# driver.net
KiCad netlist of a schematic drawn in Altium Designer
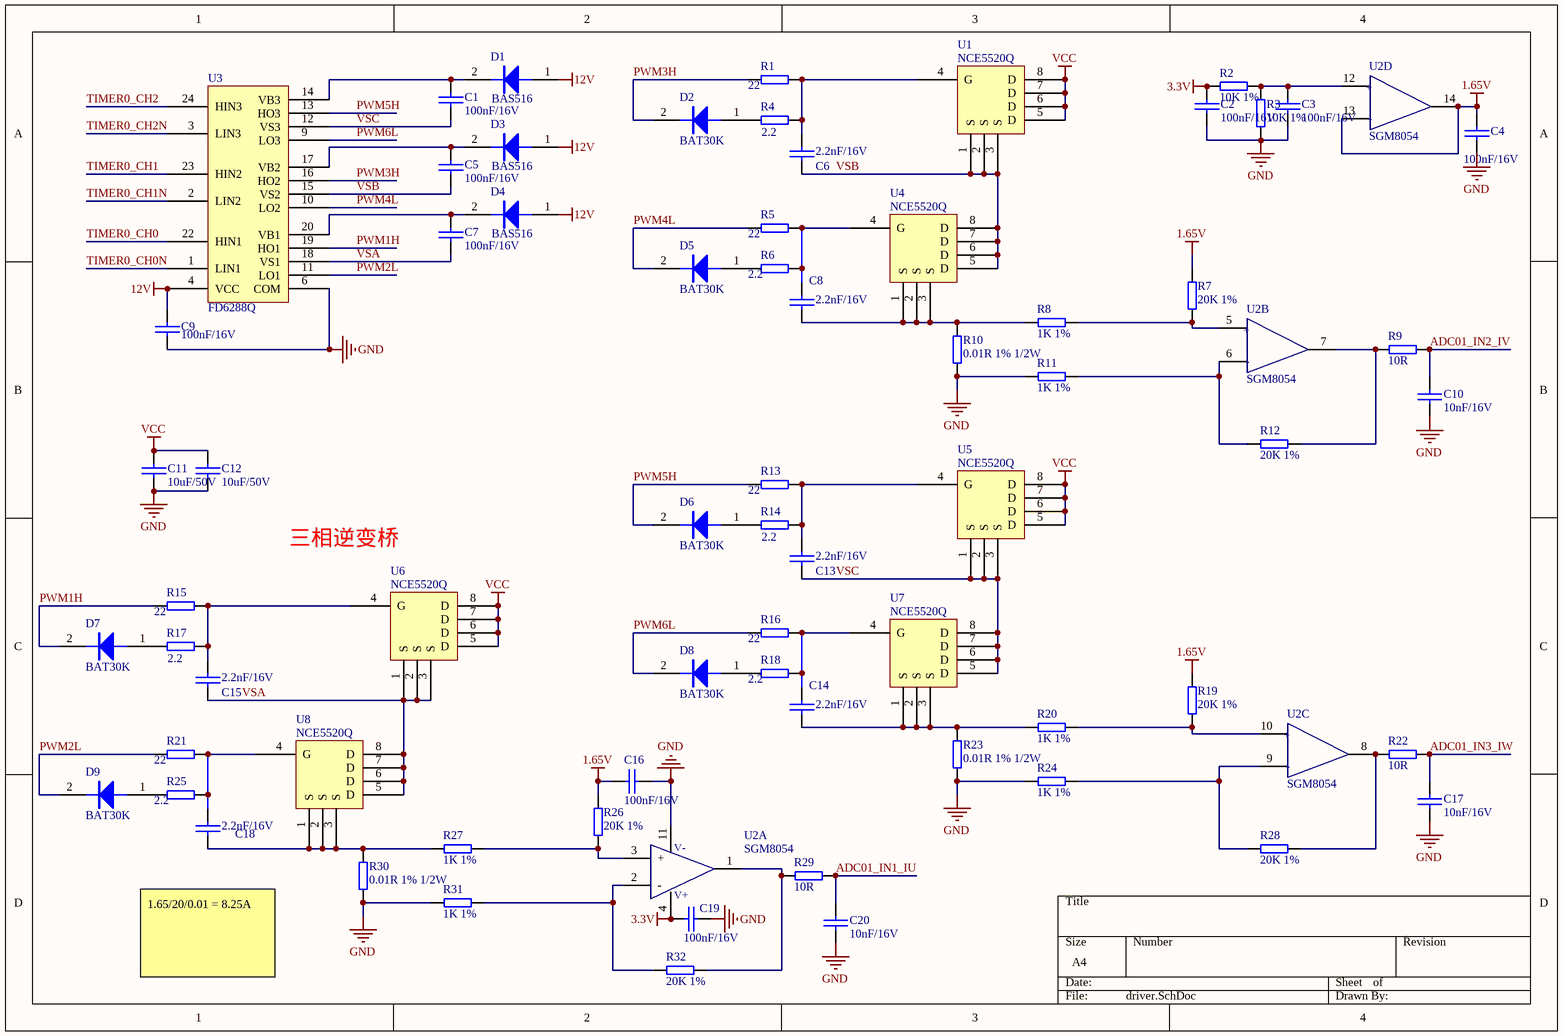
[diagram p0: driver.SchDoc]

(export (version "E")
  (design (tool "Eeschema 10.0.6"))
  (components
    (comp (ref "C1")
      (value "100nF/16V")
      (footprint "C0402")
      (description "Capacitor")
      (libsource (lib "*") (part "CAP"))
    )
    (comp (ref "C2")
      (value "100nF/16V")
      (footprint "C0402")
      (description "Capacitor")
      (libsource (lib "*") (part "CAP"))
    )
    (comp (ref "C3")
      (value "100nF/16V")
      (footprint "C0402")
      (description "Capacitor")
      (libsource (lib "*") (part "CAP"))
    )
    (comp (ref "C4")
      (value "100nF/16V")
      (footprint "C0402")
      (description "Capacitor")
      (libsource (lib "*") (part "CAP"))
    )
    (comp (ref "C5")
      (value "100nF/16V")
      (footprint "C0402")
      (description "Capacitor")
      (libsource (lib "*") (part "CAP"))
    )
    (comp (ref "C6")
      (value "2.2nF/16V")
      (footprint "C0402")
      (description "Capacitor")
      (libsource (lib "*") (part "CAP"))
    )
    (comp (ref "C7")
      (value "100nF/16V")
      (footprint "C0402")
      (description "Capacitor")
      (libsource (lib "*") (part "CAP"))
    )
    (comp (ref "C8")
      (value "2.2nF/16V")
      (footprint "C0402")
      (description "Capacitor")
      (libsource (lib "*") (part "CAP"))
    )
    (comp (ref "C9")
      (value "100nF/16V")
      (footprint "C0402")
      (description "Capacitor")
      (libsource (lib "*") (part "CAP"))
    )
    (comp (ref "C10")
      (value "10nF/16V")
      (footprint "C0402")
      (description "Capacitor")
      (libsource (lib "*") (part "CAP"))
    )
    (comp (ref "C11")
      (value "10uF/50V")
      (footprint "C1206")
      (description "Capacitor")
      (libsource (lib "*") (part "CAP"))
    )
    (comp (ref "C12")
      (value "10uF/50V")
      (footprint "C1206")
      (description "Capacitor")
      (libsource (lib "*") (part "CAP"))
    )
    (comp (ref "C13")
      (value "2.2nF/16V")
      (footprint "C0402")
      (description "Capacitor")
      (libsource (lib "*") (part "CAP"))
    )
    (comp (ref "C14")
      (value "2.2nF/16V")
      (footprint "C0402")
      (description "Capacitor")
      (libsource (lib "*") (part "CAP"))
    )
    (comp (ref "C15")
      (value "2.2nF/16V")
      (footprint "C0402")
      (description "Capacitor")
      (libsource (lib "*") (part "CAP"))
    )
    (comp (ref "C16")
      (value "100nF/16V")
      (footprint "C0402")
      (description "Capacitor")
      (libsource (lib "*") (part "CAP"))
    )
    (comp (ref "C17")
      (value "10nF/16V")
      (footprint "C0402")
      (description "Capacitor")
      (libsource (lib "*") (part "CAP"))
    )
    (comp (ref "C18")
      (value "2.2nF/16V")
      (footprint "C0402")
      (description "Capacitor")
      (libsource (lib "*") (part "CAP"))
    )
    (comp (ref "C19")
      (value "100nF/16V")
      (footprint "C0402")
      (description "Capacitor")
      (libsource (lib "*") (part "CAP"))
    )
    (comp (ref "C20")
      (value "10nF/16V")
      (footprint "C0402")
      (description "Capacitor")
      (libsource (lib "*") (part "CAP"))
    )
    (comp (ref "D1") (value "BAS516") (footprint "SOD-523/SC-79") (libsource (lib "*") (part "DIODE")))
    (comp (ref "D2") (value "BAT30K") (footprint "SOD-523/SC-79") (libsource (lib "*") (part "DIODE")))
    (comp (ref "D3") (value "BAS516") (footprint "SOD-523/SC-79") (libsource (lib "*") (part "DIODE")))
    (comp (ref "D4") (value "BAS516") (footprint "SOD-523/SC-79") (libsource (lib "*") (part "DIODE")))
    (comp (ref "D5") (value "BAT30K") (footprint "SOD-523/SC-79") (libsource (lib "*") (part "DIODE")))
    (comp (ref "D6") (value "BAT30K") (footprint "SOD-523/SC-79") (libsource (lib "*") (part "DIODE")))
    (comp (ref "D7") (value "BAT30K") (footprint "SOD-523/SC-79") (libsource (lib "*") (part "DIODE")))
    (comp (ref "D8") (value "BAT30K") (footprint "SOD-523/SC-79") (libsource (lib "*") (part "DIODE")))
    (comp (ref "D9") (value "BAT30K") (footprint "SOD-523/SC-79") (libsource (lib "*") (part "DIODE")))
    (comp (ref "R1") (value "22") (footprint "R0402") (libsource (lib "*") (part "R")))
    (comp (ref "R2") (value "10K 1%") (footprint "R0402") (libsource (lib "zijianku") (part "Resistance")))
    (comp (ref "R3") (value "10K 1%") (footprint "R0402") (libsource (lib "zijianku") (part "Resistance")))
    (comp (ref "R4") (value "2.2") (footprint "R0402") (libsource (lib "*") (part "R")))
    (comp (ref "R5") (value "22") (footprint "R0402") (libsource (lib "*") (part "R")))
    (comp (ref "R6") (value "2.2") (footprint "R0402") (libsource (lib "*") (part "R")))
    (comp (ref "R7") (value "20K 1%") (footprint "R0402") (libsource (lib "zijianku") (part "Resistance")))
    (comp (ref "R8") (value "1K 1%") (footprint "R0402") (libsource (lib "zijianku") (part "Resistance")))
    (comp (ref "R9") (value "10R") (footprint "R0402") (libsource (lib "zijianku") (part "Resistance")))
    (comp (ref "R10")
      (value "0.01R 1% 1/2W")
      (footprint "R0805")
      (libsource (lib "zijianku") (part "Resistance"))
    )
    (comp (ref "R11") (value "1K 1%") (footprint "R0402") (libsource (lib "zijianku") (part "Resistance")))
    (comp (ref "R12") (value "20K 1%") (footprint "R0402") (libsource (lib "zijianku") (part "Resistance")))
    (comp (ref "R13") (value "22") (footprint "R0402") (libsource (lib "*") (part "R")))
    (comp (ref "R14") (value "2.2") (footprint "R0402") (libsource (lib "*") (part "R")))
    (comp (ref "R15") (value "22") (footprint "R0402") (libsource (lib "*") (part "R")))
    (comp (ref "R16") (value "22") (footprint "R0402") (libsource (lib "*") (part "R")))
    (comp (ref "R17") (value "2.2") (footprint "R0402") (libsource (lib "*") (part "R")))
    (comp (ref "R18") (value "2.2") (footprint "R0402") (libsource (lib "*") (part "R")))
    (comp (ref "R19") (value "20K 1%") (footprint "R0402") (libsource (lib "zijianku") (part "Resistance")))
    (comp (ref "R20") (value "1K 1%") (footprint "R0402") (libsource (lib "zijianku") (part "Resistance")))
    (comp (ref "R21") (value "22") (footprint "R0402") (libsource (lib "*") (part "R")))
    (comp (ref "R22") (value "10R") (footprint "R0402") (libsource (lib "zijianku") (part "Resistance")))
    (comp (ref "R23")
      (value "0.01R 1% 1/2W")
      (footprint "R0805")
      (libsource (lib "zijianku") (part "Resistance"))
    )
    (comp (ref "R24") (value "1K 1%") (footprint "R0402") (libsource (lib "zijianku") (part "Resistance")))
    (comp (ref "R25") (value "2.2") (footprint "R0402") (libsource (lib "*") (part "R")))
    (comp (ref "R26") (value "20K 1%") (footprint "R0402") (libsource (lib "zijianku") (part "Resistance")))
    (comp (ref "R27") (value "1K 1%") (footprint "R0402") (libsource (lib "zijianku") (part "Resistance")))
    (comp (ref "R28") (value "20K 1%") (footprint "R0402") (libsource (lib "zijianku") (part "Resistance")))
    (comp (ref "R29") (value "10R") (footprint "R0402") (libsource (lib "zijianku") (part "Resistance")))
    (comp (ref "R30")
      (value "0.01R 1% 1/2W")
      (footprint "R0805")
      (libsource (lib "zijianku") (part "Resistance"))
    )
    (comp (ref "R31") (value "1K 1%") (footprint "R0402") (libsource (lib "zijianku") (part "Resistance")))
    (comp (ref "R32") (value "20K 1%") (footprint "R0402") (libsource (lib "zijianku") (part "Resistance")))
    (comp (ref "U1") (value "NCE5520Q") (footprint "DFN3X3-8L") (libsource (lib "*") (part "SI7465DP")))
    (comp (ref "U2") (value "SGM8054") (footprint "TSSOP-14") (libsource (lib "zijianku") (part "SGM8054")))
    (comp (ref "U3")
      (value "FD6288Q")
      (footprint "QFN_P0.5_24")
      (description "峰岹科技")
      (libsource (lib "zijianku") (part "FD6288Q"))
    )
    (comp (ref "U4") (value "NCE5520Q") (footprint "DFN3X3-8L") (libsource (lib "*") (part "SI7465DP")))
    (comp (ref "U5") (value "NCE5520Q") (footprint "DFN3X3-8L") (libsource (lib "*") (part "SI7465DP")))
    (comp (ref "U6") (value "NCE5520Q") (footprint "DFN3X3-8L") (libsource (lib "*") (part "SI7465DP")))
    (comp (ref "U7") (value "NCE5520Q") (footprint "DFN3X3-8L") (libsource (lib "*") (part "SI7465DP")))
    (comp (ref "U8") (value "NCE5520Q") (footprint "DFN3X3-8L") (libsource (lib "*") (part "SI7465DP")))
  )
  (nets
    (net (code "1") (name "/ADC01_IN1_IU") (class "Default")
      (node (ref "C20") (pin "1") (pinfunction "1_1") (pintype "passive"))
      (node (ref "R29") (pin "1") (pintype "passive"))
    )
    (net (code "2") (name "/ADC01_IN2_IV") (class "Default")
      (node (ref "C10") (pin "1") (pinfunction "1_1") (pintype "passive"))
      (node (ref "R9") (pin "1") (pintype "passive"))
    )
    (net (code "3") (name "/ADC01_IN3_IW") (class "Default")
      (node (ref "C17") (pin "1") (pinfunction "1_1") (pintype "passive"))
      (node (ref "R22") (pin "1") (pintype "passive"))
    )
    (net (code "4") (name "/PWM1H") (class "Default")
      (node (ref "D7") (pin "2") (pinfunction "K_2") (pintype "passive"))
      (node (ref "R15") (pin "2") (pinfunction "2_2") (pintype "passive"))
      (node (ref "U3") (pin "19") (pinfunction "HO1_19") (pintype "passive"))
    )
    (net (code "5") (name "/PWM2L") (class "Default")
      (node (ref "D9") (pin "2") (pinfunction "K_2") (pintype "passive"))
      (node (ref "R21") (pin "2") (pinfunction "2_2") (pintype "passive"))
      (node (ref "U3") (pin "11") (pinfunction "LO1_11") (pintype "passive"))
    )
    (net (code "6") (name "/PWM3H") (class "Default")
      (node (ref "D2") (pin "2") (pinfunction "K_2") (pintype "passive"))
      (node (ref "R1") (pin "2") (pinfunction "2_2") (pintype "passive"))
      (node (ref "U3") (pin "16") (pinfunction "HO2_16") (pintype "passive"))
    )
    (net (code "7") (name "/PWM4L") (class "Default")
      (node (ref "D5") (pin "2") (pinfunction "K_2") (pintype "passive"))
      (node (ref "R5") (pin "2") (pinfunction "2_2") (pintype "passive"))
      (node (ref "U3") (pin "10") (pinfunction "LO2_10") (pintype "passive"))
    )
    (net (code "8") (name "/PWM5H") (class "Default")
      (node (ref "D6") (pin "2") (pinfunction "K_2") (pintype "passive"))
      (node (ref "R13") (pin "2") (pinfunction "2_2") (pintype "passive"))
      (node (ref "U3") (pin "13") (pinfunction "HO3_13") (pintype "passive"))
    )
    (net (code "9") (name "/PWM6L") (class "Default")
      (node (ref "D8") (pin "2") (pinfunction "K_2") (pintype "passive"))
      (node (ref "R16") (pin "2") (pinfunction "2_2") (pintype "passive"))
      (node (ref "U3") (pin "9") (pinfunction "LO3_9") (pintype "passive"))
    )
    (net (code "10") (name "/TIMER0_CH0") (class "Default")
      (node (ref "U3") (pin "22") (pinfunction "HIN1_22") (pintype "passive"))
    )
    (net (code "11") (name "/TIMER0_CH0N") (class "Default")
      (node (ref "U3") (pin "1") (pinfunction "LIN1_1") (pintype "passive"))
    )
    (net (code "12") (name "/TIMER0_CH1") (class "Default")
      (node (ref "U3") (pin "23") (pinfunction "HIN2_23") (pintype "passive"))
    )
    (net (code "13") (name "/TIMER0_CH1N") (class "Default")
      (node (ref "U3") (pin "2") (pinfunction "LIN2_2") (pintype "passive"))
    )
    (net (code "14") (name "/TIMER0_CH2") (class "Default")
      (node (ref "U3") (pin "24") (pinfunction "HIN3_24") (pintype "passive"))
    )
    (net (code "15") (name "/TIMER0_CH2N") (class "Default")
      (node (ref "U3") (pin "3") (pinfunction "LIN3_3") (pintype "passive"))
    )
    (net (code "16") (name "/VSA") (class "Default")
      (node (ref "C15") (pin "2") (pinfunction "2_2") (pintype "passive"))
      (node (ref "C7") (pin "1") (pinfunction "1_1") (pintype "passive"))
      (node (ref "U3") (pin "18") (pinfunction "VS1_18") (pintype "passive"))
      (node (ref "U6") (pin "1") (pinfunction "S_1") (pintype "passive"))
      (node (ref "U6") (pin "2") (pinfunction "S_2") (pintype "passive"))
      (node (ref "U6") (pin "3") (pinfunction "S_3") (pintype "passive"))
      (node (ref "U8") (pin "5") (pinfunction "D_5") (pintype "passive"))
      (node (ref "U8") (pin "6") (pinfunction "D_6") (pintype "passive"))
      (node (ref "U8") (pin "7") (pinfunction "D_7") (pintype "passive"))
      (node (ref "U8") (pin "8") (pinfunction "D_8") (pintype "passive"))
    )
    (net (code "17") (name "/VSB") (class "Default")
      (node (ref "C5") (pin "1") (pinfunction "1_1") (pintype "passive"))
      (node (ref "C6") (pin "2") (pinfunction "2_2") (pintype "passive"))
      (node (ref "U1") (pin "1") (pinfunction "S_1") (pintype "passive"))
      (node (ref "U1") (pin "2") (pinfunction "S_2") (pintype "passive"))
      (node (ref "U1") (pin "3") (pinfunction "S_3") (pintype "passive"))
      (node (ref "U3") (pin "15") (pinfunction "VS2_15") (pintype "passive"))
      (node (ref "U4") (pin "5") (pinfunction "D_5") (pintype "passive"))
      (node (ref "U4") (pin "6") (pinfunction "D_6") (pintype "passive"))
      (node (ref "U4") (pin "7") (pinfunction "D_7") (pintype "passive"))
      (node (ref "U4") (pin "8") (pinfunction "D_8") (pintype "passive"))
    )
    (net (code "18") (name "/VSC") (class "Default")
      (node (ref "C1") (pin "1") (pinfunction "1_1") (pintype "passive"))
      (node (ref "C13") (pin "2") (pinfunction "2_2") (pintype "passive"))
      (node (ref "U3") (pin "12") (pinfunction "VS3_12") (pintype "passive"))
      (node (ref "U5") (pin "1") (pinfunction "S_1") (pintype "passive"))
      (node (ref "U5") (pin "2") (pinfunction "S_2") (pintype "passive"))
      (node (ref "U5") (pin "3") (pinfunction "S_3") (pintype "passive"))
      (node (ref "U7") (pin "5") (pinfunction "D_5") (pintype "passive"))
      (node (ref "U7") (pin "6") (pinfunction "D_6") (pintype "passive"))
      (node (ref "U7") (pin "7") (pinfunction "D_7") (pintype "passive"))
      (node (ref "U7") (pin "8") (pinfunction "D_8") (pintype "passive"))
    )
    (net (code "19") (name "1.65V") (class "Default")
      (node (ref "C16") (pin "2") (pinfunction "2_2") (pintype "passive"))
      (node (ref "C4") (pin "1") (pinfunction "1_1") (pintype "passive"))
      (node (ref "R19") (pin "1") (pintype "passive"))
      (node (ref "R26") (pin "1") (pintype "passive"))
      (node (ref "R7") (pin "1") (pintype "passive"))
      (node (ref "U2") (pin "13") (pinfunction "-_13") (pintype "passive"))
      (node (ref "U2") (pin "14") (pinfunction "OUT2_14") (pintype "passive"))
    )
    (net (code "20") (name "3.3V") (class "Default")
      (node (ref "C19") (pin "2") (pinfunction "2_2") (pintype "passive"))
      (node (ref "C2") (pin "1") (pinfunction "1_1") (pintype "passive"))
      (node (ref "R2") (pin "1") (pintype "passive"))
      (node (ref "U2") (pin "4") (pinfunction "V+_4") (pintype "passive"))
    )
    (net (code "21") (name "12V") (class "Default")
      (node (ref "C9") (pin "2") (pinfunction "2_2") (pintype "passive"))
      (node (ref "D1") (pin "1") (pinfunction "A_1") (pintype "passive"))
      (node (ref "D3") (pin "1") (pinfunction "A_1") (pintype "passive"))
      (node (ref "D4") (pin "1") (pinfunction "A_1") (pintype "passive"))
      (node (ref "U3") (pin "4") (pinfunction "VCC_4") (pintype "passive"))
    )
    (net (code "22") (name "GND") (class "Default")
      (node (ref "C10") (pin "2") (pinfunction "2_2") (pintype "passive"))
      (node (ref "C11") (pin "2") (pinfunction "2_2") (pintype "passive"))
      (node (ref "C12") (pin "2") (pinfunction "2_2") (pintype "passive"))
      (node (ref "C16") (pin "1") (pinfunction "1_1") (pintype "passive"))
      (node (ref "C17") (pin "2") (pinfunction "2_2") (pintype "passive"))
      (node (ref "C19") (pin "1") (pinfunction "1_1") (pintype "passive"))
      (node (ref "C2") (pin "2") (pinfunction "2_2") (pintype "passive"))
      (node (ref "C20") (pin "2") (pinfunction "2_2") (pintype "passive"))
      (node (ref "C3") (pin "2") (pinfunction "2_2") (pintype "passive"))
      (node (ref "C4") (pin "2") (pinfunction "2_2") (pintype "passive"))
      (node (ref "C9") (pin "1") (pinfunction "1_1") (pintype "passive"))
      (node (ref "R10") (pin "2") (pintype "passive"))
      (node (ref "R11") (pin "2") (pintype "passive"))
      (node (ref "R23") (pin "2") (pintype "passive"))
      (node (ref "R24") (pin "2") (pintype "passive"))
      (node (ref "R3") (pin "2") (pintype "passive"))
      (node (ref "R30") (pin "2") (pintype "passive"))
      (node (ref "R31") (pin "2") (pintype "passive"))
      (node (ref "U2") (pin "11") (pinfunction "V-_11") (pintype "passive"))
      (node (ref "U3") (pin "6") (pinfunction "COM_6") (pintype "passive"))
    )
    (net (code "23") (name "Net-(C8-Pad2)") (class "Default")
      (node (ref "C8") (pin "2") (pinfunction "2_2") (pintype "passive"))
      (node (ref "R10") (pin "1") (pintype "passive"))
      (node (ref "R8") (pin "2") (pintype "passive"))
      (node (ref "U4") (pin "1") (pinfunction "S_1") (pintype "passive"))
      (node (ref "U4") (pin "2") (pinfunction "S_2") (pintype "passive"))
      (node (ref "U4") (pin "3") (pinfunction "S_3") (pintype "passive"))
    )
    (net (code "24") (name "Net-(C14-Pad2)") (class "Default")
      (node (ref "C14") (pin "2") (pinfunction "2_2") (pintype "passive"))
      (node (ref "R20") (pin "2") (pintype "passive"))
      (node (ref "R23") (pin "1") (pintype "passive"))
      (node (ref "U7") (pin "1") (pinfunction "S_1") (pintype "passive"))
      (node (ref "U7") (pin "2") (pinfunction "S_2") (pintype "passive"))
      (node (ref "U7") (pin "3") (pinfunction "S_3") (pintype "passive"))
    )
    (net (code "25") (name "Net-(C18-Pad2)") (class "Default")
      (node (ref "C18") (pin "2") (pinfunction "2_2") (pintype "passive"))
      (node (ref "R27") (pin "2") (pintype "passive"))
      (node (ref "R30") (pin "1") (pintype "passive"))
      (node (ref "U8") (pin "1") (pinfunction "S_1") (pintype "passive"))
      (node (ref "U8") (pin "2") (pinfunction "S_2") (pintype "passive"))
      (node (ref "U8") (pin "3") (pinfunction "S_3") (pintype "passive"))
    )
    (net (code "26") (name "Net-(D1-K)") (class "Default")
      (node (ref "C1") (pin "2") (pinfunction "2_2") (pintype "passive"))
      (node (ref "D1") (pin "2") (pinfunction "K_2") (pintype "passive"))
      (node (ref "U3") (pin "14") (pinfunction "VB3_14") (pintype "passive"))
    )
    (net (code "27") (name "Net-(D2-A)") (class "Default")
      (node (ref "D2") (pin "1") (pinfunction "A_1") (pintype "passive"))
      (node (ref "R4") (pin "1") (pinfunction "1_1") (pintype "passive"))
    )
    (net (code "28") (name "Net-(D3-K)") (class "Default")
      (node (ref "C5") (pin "2") (pinfunction "2_2") (pintype "passive"))
      (node (ref "D3") (pin "2") (pinfunction "K_2") (pintype "passive"))
      (node (ref "U3") (pin "17") (pinfunction "VB2_17") (pintype "passive"))
    )
    (net (code "29") (name "Net-(D4-K)") (class "Default")
      (node (ref "C7") (pin "2") (pinfunction "2_2") (pintype "passive"))
      (node (ref "D4") (pin "2") (pinfunction "K_2") (pintype "passive"))
      (node (ref "U3") (pin "20") (pinfunction "VB1_20") (pintype "passive"))
    )
    (net (code "30") (name "Net-(D5-A)") (class "Default")
      (node (ref "D5") (pin "1") (pinfunction "A_1") (pintype "passive"))
      (node (ref "R6") (pin "1") (pinfunction "1_1") (pintype "passive"))
    )
    (net (code "31") (name "Net-(D6-A)") (class "Default")
      (node (ref "D6") (pin "1") (pinfunction "A_1") (pintype "passive"))
      (node (ref "R14") (pin "1") (pinfunction "1_1") (pintype "passive"))
    )
    (net (code "32") (name "Net-(D7-A)") (class "Default")
      (node (ref "D7") (pin "1") (pinfunction "A_1") (pintype "passive"))
      (node (ref "R17") (pin "1") (pinfunction "1_1") (pintype "passive"))
    )
    (net (code "33") (name "Net-(D8-A)") (class "Default")
      (node (ref "D8") (pin "1") (pinfunction "A_1") (pintype "passive"))
      (node (ref "R18") (pin "1") (pinfunction "1_1") (pintype "passive"))
    )
    (net (code "34") (name "Net-(D9-A)") (class "Default")
      (node (ref "D9") (pin "1") (pinfunction "A_1") (pintype "passive"))
      (node (ref "R25") (pin "1") (pinfunction "1_1") (pintype "passive"))
    )
    (net (code "35") (name "Net-(U1-G)") (class "Default")
      (node (ref "C6") (pin "1") (pinfunction "1_1") (pintype "passive"))
      (node (ref "R1") (pin "1") (pinfunction "1_1") (pintype "passive"))
      (node (ref "R4") (pin "2") (pinfunction "2_2") (pintype "passive"))
      (node (ref "U1") (pin "4") (pinfunction "G_4") (pintype "passive"))
    )
    (net (code "36") (name "Net-(U2A-+)") (class "Default")
      (node (ref "R26") (pin "2") (pintype "passive"))
      (node (ref "R27") (pin "1") (pintype "passive"))
      (node (ref "U2") (pin "3") (pinfunction "+_3") (pintype "passive"))
    )
    (net (code "37") (name "Net-(U2A--)") (class "Default")
      (node (ref "R31") (pin "1") (pintype "passive"))
      (node (ref "R32") (pin "2") (pintype "passive"))
      (node (ref "U2") (pin "2") (pinfunction "-_2") (pintype "passive"))
    )
    (net (code "38") (name "Net-(U2A-OUT1)") (class "Default")
      (node (ref "R29") (pin "2") (pintype "passive"))
      (node (ref "R32") (pin "1") (pintype "passive"))
      (node (ref "U2") (pin "1") (pinfunction "OUT1_1") (pintype "passive"))
    )
    (net (code "39") (name "Net-(U2B-+)") (class "Default")
      (node (ref "R7") (pin "2") (pintype "passive"))
      (node (ref "R8") (pin "1") (pintype "passive"))
      (node (ref "U2") (pin "5") (pinfunction "+_5") (pintype "passive"))
    )
    (net (code "40") (name "Net-(U2B--)") (class "Default")
      (node (ref "R11") (pin "1") (pintype "passive"))
      (node (ref "R12") (pin "2") (pintype "passive"))
      (node (ref "U2") (pin "6") (pinfunction "-_6") (pintype "passive"))
    )
    (net (code "41") (name "Net-(U2B-OUT2)") (class "Default")
      (node (ref "R12") (pin "1") (pintype "passive"))
      (node (ref "R9") (pin "2") (pintype "passive"))
      (node (ref "U2") (pin "7") (pinfunction "OUT2_7") (pintype "passive"))
    )
    (net (code "42") (name "Net-(U2C-+)") (class "Default")
      (node (ref "R19") (pin "2") (pintype "passive"))
      (node (ref "R20") (pin "1") (pintype "passive"))
      (node (ref "U2") (pin "10") (pinfunction "+_10") (pintype "passive"))
    )
    (net (code "43") (name "Net-(U2C--)") (class "Default")
      (node (ref "R24") (pin "1") (pintype "passive"))
      (node (ref "R28") (pin "2") (pintype "passive"))
      (node (ref "U2") (pin "9") (pinfunction "-_9") (pintype "passive"))
    )
    (net (code "44") (name "Net-(U2C-OUT2)") (class "Default")
      (node (ref "R22") (pin "2") (pintype "passive"))
      (node (ref "R28") (pin "1") (pintype "passive"))
      (node (ref "U2") (pin "8") (pinfunction "OUT2_8") (pintype "passive"))
    )
    (net (code "45") (name "Net-(U2D-+)") (class "Default")
      (node (ref "C3") (pin "1") (pinfunction "1_1") (pintype "passive"))
      (node (ref "R2") (pin "2") (pintype "passive"))
      (node (ref "R3") (pin "1") (pintype "passive"))
      (node (ref "U2") (pin "12") (pinfunction "+_12") (pintype "passive"))
    )
    (net (code "46") (name "Net-(U4-G)") (class "Default")
      (node (ref "C8") (pin "1") (pinfunction "1_1") (pintype "passive"))
      (node (ref "R5") (pin "1") (pinfunction "1_1") (pintype "passive"))
      (node (ref "R6") (pin "2") (pinfunction "2_2") (pintype "passive"))
      (node (ref "U4") (pin "4") (pinfunction "G_4") (pintype "passive"))
    )
    (net (code "47") (name "Net-(U5-G)") (class "Default")
      (node (ref "C13") (pin "1") (pinfunction "1_1") (pintype "passive"))
      (node (ref "R13") (pin "1") (pinfunction "1_1") (pintype "passive"))
      (node (ref "R14") (pin "2") (pinfunction "2_2") (pintype "passive"))
      (node (ref "U5") (pin "4") (pinfunction "G_4") (pintype "passive"))
    )
    (net (code "48") (name "Net-(U6-G)") (class "Default")
      (node (ref "C15") (pin "1") (pinfunction "1_1") (pintype "passive"))
      (node (ref "R15") (pin "1") (pinfunction "1_1") (pintype "passive"))
      (node (ref "R17") (pin "2") (pinfunction "2_2") (pintype "passive"))
      (node (ref "U6") (pin "4") (pinfunction "G_4") (pintype "passive"))
    )
    (net (code "49") (name "Net-(U7-G)") (class "Default")
      (node (ref "C14") (pin "1") (pinfunction "1_1") (pintype "passive"))
      (node (ref "R16") (pin "1") (pinfunction "1_1") (pintype "passive"))
      (node (ref "R18") (pin "2") (pinfunction "2_2") (pintype "passive"))
      (node (ref "U7") (pin "4") (pinfunction "G_4") (pintype "passive"))
    )
    (net (code "50") (name "Net-(U8-G)") (class "Default")
      (node (ref "C18") (pin "1") (pinfunction "1_1") (pintype "passive"))
      (node (ref "R21") (pin "1") (pinfunction "1_1") (pintype "passive"))
      (node (ref "R25") (pin "2") (pinfunction "2_2") (pintype "passive"))
      (node (ref "U8") (pin "4") (pinfunction "G_4") (pintype "passive"))
    )
    (net (code "51") (name "VCC") (class "Default")
      (node (ref "C11") (pin "1") (pinfunction "1_1") (pintype "passive"))
      (node (ref "C12") (pin "1") (pinfunction "1_1") (pintype "passive"))
      (node (ref "U1") (pin "5") (pinfunction "D_5") (pintype "passive"))
      (node (ref "U1") (pin "6") (pinfunction "D_6") (pintype "passive"))
      (node (ref "U1") (pin "7") (pinfunction "D_7") (pintype "passive"))
      (node (ref "U1") (pin "8") (pinfunction "D_8") (pintype "passive"))
      (node (ref "U5") (pin "5") (pinfunction "D_5") (pintype "passive"))
      (node (ref "U5") (pin "6") (pinfunction "D_6") (pintype "passive"))
      (node (ref "U5") (pin "7") (pinfunction "D_7") (pintype "passive"))
      (node (ref "U5") (pin "8") (pinfunction "D_8") (pintype "passive"))
      (node (ref "U6") (pin "5") (pinfunction "D_5") (pintype "passive"))
      (node (ref "U6") (pin "6") (pinfunction "D_6") (pintype "passive"))
      (node (ref "U6") (pin "7") (pinfunction "D_7") (pintype "passive"))
      (node (ref "U6") (pin "8") (pinfunction "D_8") (pintype "passive"))
    )
  )
)
